# LCD_MicroSD.net
KiCad netlist of a schematic drawn in Altium Designer
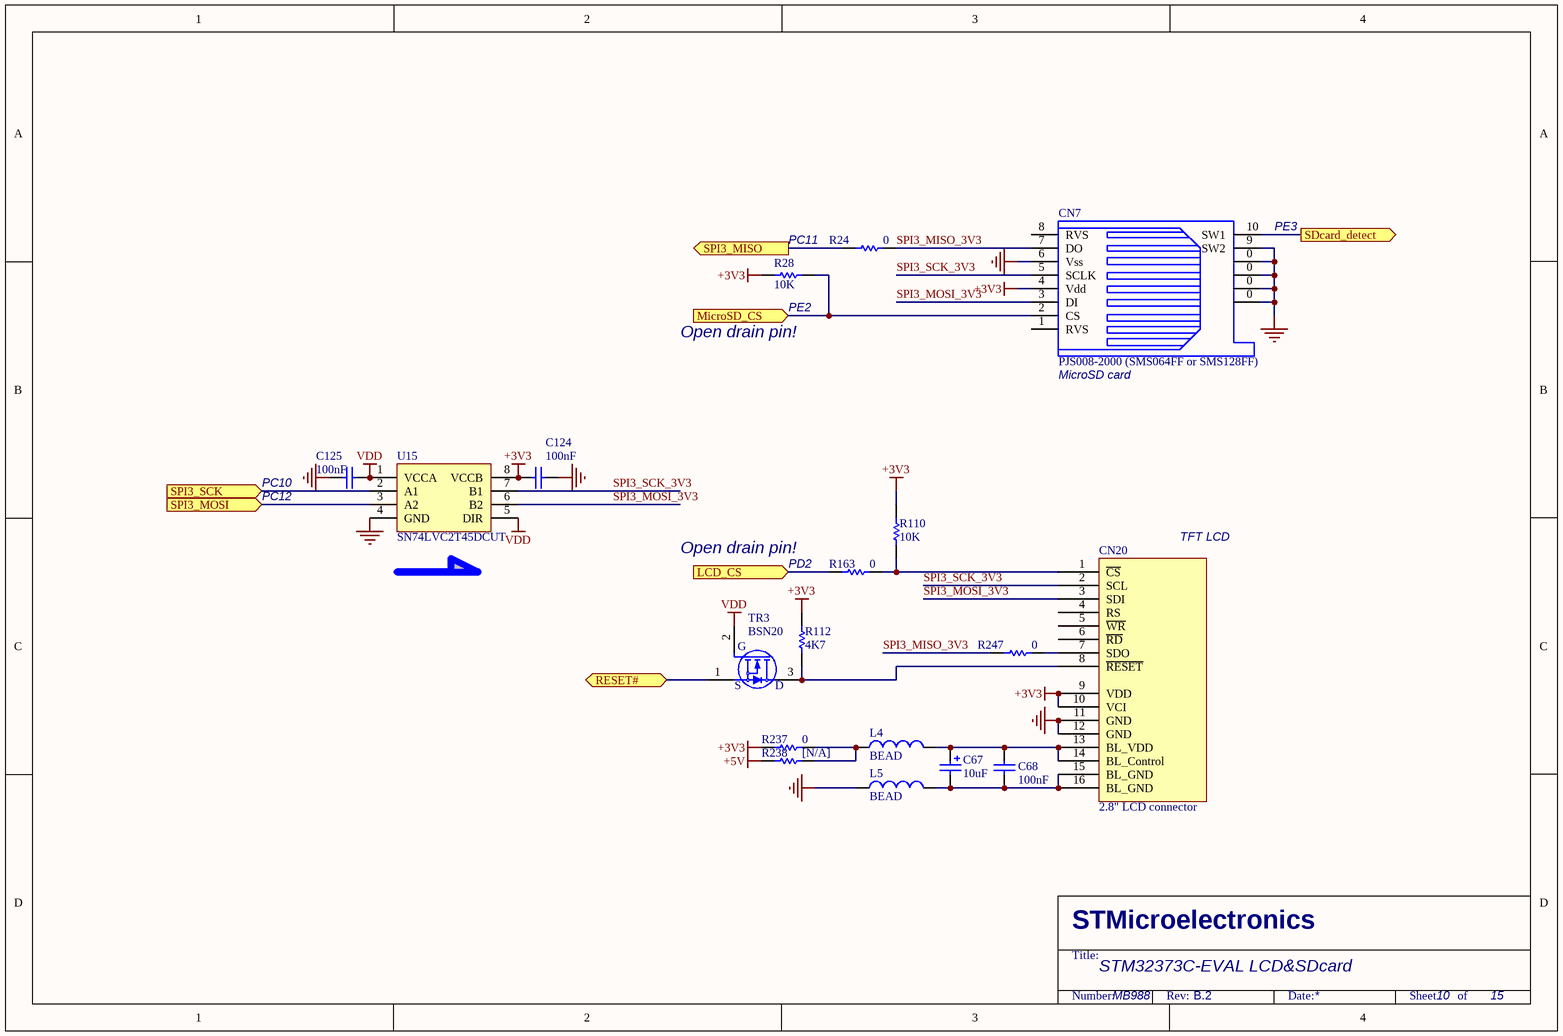
[diagram p0: LCD_MicroSD.SchDoc]

(export (version "E")
  (design (tool "Eeschema 10.0.6"))
  (components
    (comp (ref "C67")
      (value "10uF")
      (footprint "TAN-A")
      (description "Polarized Capacitor (Radial)")
      (fields (field (name "PUBLISHER") "Altium Limited"))
      (libsource (lib "Miscellaneous Devices") (part "Cap Pol1"))
    )
    (comp (ref "C68")
      (value "100nF")
      (footprint "0603C")
      (description "Capacitor")
      (fields (field (name "PUBLISHER") "Altium Limited"))
      (libsource (lib "Miscellaneous Devices") (part "Cap"))
    )
    (comp (ref "C124")
      (value "100nF")
      (footprint "0603C")
      (description "Capacitor")
      (fields (field (name "PUBLISHER") "Altium Limited"))
      (libsource (lib "Miscellaneous Devices") (part "CAP"))
    )
    (comp (ref "C125")
      (value "100nF")
      (footprint "0603C")
      (description "Capacitor")
      (fields (field (name "PUBLISHER") "Altium Limited"))
      (libsource (lib "Miscellaneous Devices") (part "CAP"))
    )
    (comp (ref "CN7")
      (value "PJS008-2000 (SMS064FF or SMS128FF)")
      (footprint "MSD(PJS008)")
      (libsource (lib "MB525") (part "SMS016AFA5E"))
    )
    (comp (ref "CN20")
      (value "2.8\" LCD connector")
      (footprint "MB989")
      (libsource (lib "MB988") (part "ColorLCD_module"))
    )
    (comp (ref "L4")
      (value "BEAD")
      (footprint "0603L")
      (description "Inductor")
      (fields (field (name "PUBLISHER") "Altium Limited"))
      (libsource (lib "Miscellaneous Devices") (part "Inductor"))
    )
    (comp (ref "L5")
      (value "BEAD")
      (footprint "0603L")
      (description "Inductor")
      (fields (field (name "PUBLISHER") "Altium Limited"))
      (libsource (lib "Miscellaneous Devices") (part "Inductor"))
    )
    (comp (ref "R24")
      (value "0")
      (footprint "0603R")
      (description "Resistor")
      (fields (field (name "PUBLISHER") "Altium Limited"))
      (libsource (lib "Miscellaneous Devices") (part "Res1"))
    )
    (comp (ref "R28")
      (value "10K")
      (footprint "0603R")
      (description "Resistor")
      (fields (field (name "PUBLISHER") "Altium Limited"))
      (libsource (lib "Miscellaneous Devices") (part "Res1"))
    )
    (comp (ref "R110")
      (value "10K")
      (footprint "0603R")
      (description "Resistor")
      (fields (field (name "PUBLISHER") "Altium Limited"))
      (libsource (lib "Miscellaneous Devices") (part "Res1"))
    )
    (comp (ref "R112")
      (value "4K7")
      (footprint "0603R")
      (description "Resistor")
      (fields (field (name "PUBLISHER") "Altium Limited"))
      (libsource (lib "Miscellaneous Devices") (part "Res1"))
    )
    (comp (ref "R163")
      (value "0")
      (footprint "0603R")
      (description "Resistor")
      (fields (field (name "PUBLISHER") "Altium Limited"))
      (libsource (lib "Miscellaneous Devices") (part "Res1"))
    )
    (comp (ref "R237")
      (value "0")
      (footprint "0603R")
      (description "Resistor")
      (fields (field (name "PUBLISHER") "Altium Limited"))
      (libsource (lib "Miscellaneous Devices") (part "Res1"))
    )
    (comp (ref "R238")
      (value "[N/A]")
      (footprint "0603R")
      (description "Resistor")
      (fields (field (name "PUBLISHER") "Altium Limited"))
      (libsource (lib "Miscellaneous Devices") (part "Res1"))
    )
    (comp (ref "R247")
      (value "0")
      (footprint "0603R")
      (description "Resistor")
      (fields (field (name "PUBLISHER") "Altium Limited"))
      (libsource (lib "Miscellaneous Devices") (part "res1"))
    )
    (comp (ref "TR3") (value "BSN20") (footprint "SOT-23") (libsource (lib "MB525") (part "2N7000")))
    (comp (ref "U15")
      (value "SN74LVC2T45DCUT")
      (footprint "VSSOP8")
      (libsource (lib "MB818") (part "SN74LVC2T45DCUT"))
    )
  )
  (nets
    (net (code "1") (name "+3V3") (class "Default")
      (node (ref "C124") (pin "2") (pinfunction "2_2") (pintype "passive"))
      (node (ref "CN20") (pin "10") (pinfunction "VCI_10") (pintype "passive"))
      (node (ref "CN20") (pin "9") (pinfunction "VDD_9") (pintype "passive"))
      (node (ref "CN7") (pin "4") (pinfunction "Vdd_4") (pintype "passive"))
      (node (ref "R110") (pin "2") (pinfunction "2_2") (pintype "passive"))
      (node (ref "R112") (pin "2") (pinfunction "2_2") (pintype "passive"))
      (node (ref "R237") (pin "1") (pinfunction "1_1") (pintype "passive"))
      (node (ref "R28") (pin "2") (pinfunction "2_2") (pintype "passive"))
      (node (ref "U15") (pin "8") (pinfunction "VCCB_8") (pintype "passive"))
    )
    (net (code "2") (name "+5V") (class "Default")
      (node (ref "R238") (pin "1") (pinfunction "1_1") (pintype "passive"))
    )
    (net (code "3") (name "/LCD_CS") (class "Default")
      (node (ref "R163") (pin "2") (pinfunction "2_2") (pintype "passive"))
    )
    (net (code "4") (name "/MicroSD_CS") (class "Default")
      (node (ref "CN7") (pin "2") (pinfunction "CS_2") (pintype "passive"))
      (node (ref "R28") (pin "1") (pinfunction "1_1") (pintype "passive"))
    )
    (net (code "5") (name "/RESET#") (class "Default")
      (node (ref "TR3") (pin "1") (pinfunction "S_1") (pintype "passive"))
    )
    (net (code "6") (name "/SDcard_detect") (class "Default")
      (node (ref "CN7") (pin "10") (pinfunction "SW1_10") (pintype "passive"))
    )
    (net (code "7") (name "/SPI3_MISO") (class "Default")
      (node (ref "R24") (pin "1") (pinfunction "1_1") (pintype "passive"))
    )
    (net (code "8") (name "/SPI3_MISO_3V3") (class "Default")
      (node (ref "CN7") (pin "7") (pinfunction "DO_7") (pintype "passive"))
      (node (ref "R24") (pin "2") (pinfunction "2_2") (pintype "passive"))
      (node (ref "R247") (pin "2") (pinfunction "2_2") (pintype "passive"))
    )
    (net (code "9") (name "/SPI3_MOSI") (class "Default")
      (node (ref "U15") (pin "3") (pinfunction "A2_3") (pintype "passive"))
    )
    (net (code "10") (name "/SPI3_MOSI_3V3") (class "Default")
      (node (ref "CN20") (pin "3") (pinfunction "SDI_3") (pintype "passive"))
      (node (ref "CN7") (pin "3") (pinfunction "DI_3") (pintype "passive"))
      (node (ref "U15") (pin "6") (pinfunction "B2_6") (pintype "passive"))
    )
    (net (code "11") (name "/SPI3_SCK") (class "Default")
      (node (ref "U15") (pin "2") (pinfunction "A1_2") (pintype "passive"))
    )
    (net (code "12") (name "/SPI3_SCK_3V3") (class "Default")
      (node (ref "CN20") (pin "2") (pinfunction "SCL_2") (pintype "passive"))
      (node (ref "CN7") (pin "5") (pinfunction "SCLK_5") (pintype "passive"))
      (node (ref "U15") (pin "7") (pinfunction "B1_7") (pintype "passive"))
    )
    (net (code "13") (name "GND") (class "Default")
      (node (ref "C124") (pin "1") (pinfunction "1_1") (pintype "passive"))
      (node (ref "C125") (pin "1") (pinfunction "1_1") (pintype "passive"))
      (node (ref "CN20") (pin "11") (pinfunction "GND_11") (pintype "passive"))
      (node (ref "CN20") (pin "12") (pinfunction "GND_12") (pintype "passive"))
      (node (ref "CN7") (pin "0") (pintype "passive"))
      (node (ref "CN7") (pin "6") (pinfunction "Vss_6") (pintype "passive"))
      (node (ref "CN7") (pin "9") (pinfunction "SW2_9") (pintype "passive"))
      (node (ref "L5") (pin "1") (pinfunction "1_1") (pintype "passive"))
      (node (ref "U15") (pin "4") (pinfunction "GND_4") (pintype "passive"))
    )
    (net (code "14") (name "Net-(C67-Pad2)") (class "Default")
      (node (ref "C67") (pin "2") (pinfunction "2_2") (pintype "passive"))
      (node (ref "C68") (pin "2") (pinfunction "2_2") (pintype "passive"))
      (node (ref "CN20") (pin "15") (pinfunction "BL_GND_15") (pintype "passive"))
      (node (ref "CN20") (pin "16") (pinfunction "BL_GND_16") (pintype "passive"))
      (node (ref "L5") (pin "2") (pinfunction "2_2") (pintype "passive"))
    )
    (net (code "15") (name "Net-(CN20-BL_Control)") (class "Default")
      (node (ref "C67") (pin "1") (pinfunction "1_1") (pintype "passive"))
      (node (ref "C68") (pin "1") (pinfunction "1_1") (pintype "passive"))
      (node (ref "CN20") (pin "13") (pinfunction "BL_VDD_13") (pintype "passive"))
      (node (ref "CN20") (pin "14") (pinfunction "BL_Control_14") (pintype "passive"))
      (node (ref "L4") (pin "2") (pinfunction "2_2") (pintype "passive"))
    )
    (net (code "16") (name "Net-(CN20-SDO)") (class "Default")
      (node (ref "CN20") (pin "7") (pinfunction "SDO_7") (pintype "passive"))
      (node (ref "R247") (pin "1") (pinfunction "1_1") (pintype "passive"))
    )
    (net (code "17") (name "Net-(CN20-~{CS})") (class "Default")
      (node (ref "CN20") (pin "1") (pinfunction "~{CS}_1") (pintype "passive"))
      (node (ref "R110") (pin "1") (pinfunction "1_1") (pintype "passive"))
      (node (ref "R163") (pin "1") (pinfunction "1_1") (pintype "passive"))
    )
    (net (code "18") (name "Net-(CN20-~{RESET})") (class "Default")
      (node (ref "CN20") (pin "8") (pinfunction "~{RESET}_8") (pintype "passive"))
      (node (ref "R112") (pin "1") (pinfunction "1_1") (pintype "passive"))
      (node (ref "TR3") (pin "3") (pinfunction "D_3") (pintype "passive"))
    )
    (net (code "19") (name "Net-(L4-Pad1)") (class "Default")
      (node (ref "L4") (pin "1") (pinfunction "1_1") (pintype "passive"))
      (node (ref "R237") (pin "2") (pinfunction "2_2") (pintype "passive"))
      (node (ref "R238") (pin "2") (pinfunction "2_2") (pintype "passive"))
    )
    (net (code "20") (name "VDD") (class "Default")
      (node (ref "C125") (pin "2") (pinfunction "2_2") (pintype "passive"))
      (node (ref "TR3") (pin "2") (pinfunction "G_2") (pintype "passive"))
      (node (ref "U15") (pin "1") (pinfunction "VCCA_1") (pintype "passive"))
      (node (ref "U15") (pin "5") (pinfunction "DIR_5") (pintype "passive"))
    )
    (net (code "21") (name "unconnected-(CN7-RVS-Pad1)") (class "Default")
      (node (ref "CN7") (pin "1") (pinfunction "RVS_1") (pintype "passive"))
    )
    (net (code "22") (name "unconnected-(CN7-RVS-Pad8)") (class "Default")
      (node (ref "CN7") (pin "8") (pinfunction "RVS_8") (pintype "passive"))
    )
    (net (code "23") (name "unconnected-(CN20-RS-Pad4)") (class "Default")
      (node (ref "CN20") (pin "4") (pinfunction "RS_4") (pintype "passive"))
    )
    (net (code "24") (name "unconnected-(CN20-~{RD}-Pad6)") (class "Default")
      (node (ref "CN20") (pin "6") (pinfunction "~{RD}_6") (pintype "passive"))
    )
    (net (code "25") (name "unconnected-(CN20-~{WR}-Pad5)") (class "Default")
      (node (ref "CN20") (pin "5") (pinfunction "~{WR}_5") (pintype "passive"))
    )
  )
)
